# Sheet5.net
KiCad netlist of a schematic drawn in Altium Designer
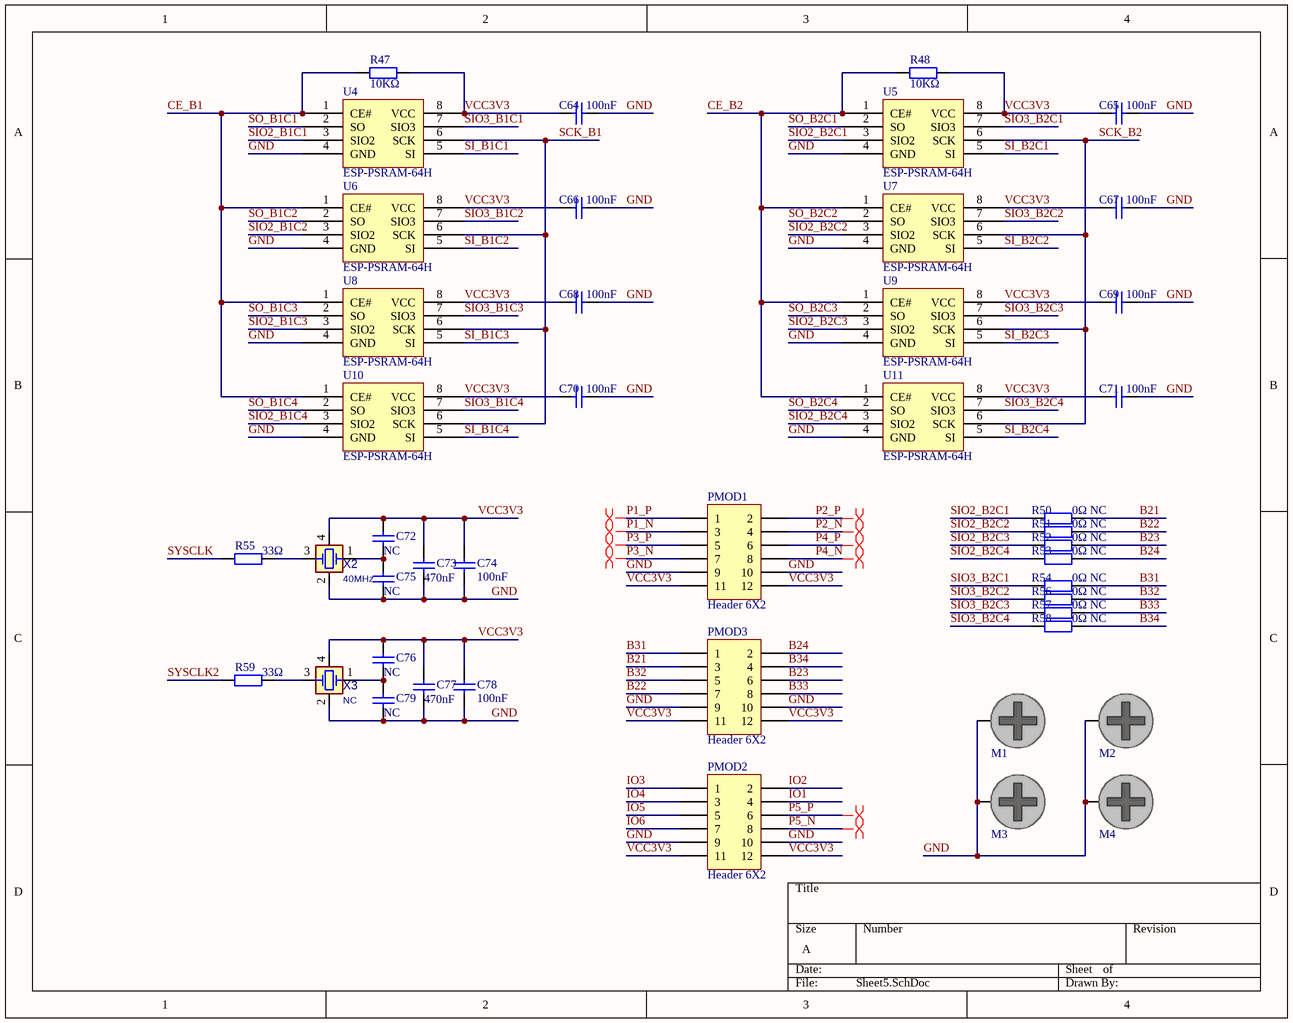
[diagram p0: Sheet5.SchDoc]

(export (version "E")
  (design (tool "Eeschema 10.0.6"))
  (components
    (comp (ref "C64")
      (value "100nF")
      (footprint "1206_C")
      (description "贴片电容")
      (libsource (lib "Cap") (part "1206 100nF (104) 10% 50V"))
    )
    (comp (ref "C65")
      (value "100nF")
      (footprint "1206_C")
      (description "贴片电容")
      (libsource (lib "Cap") (part "1206 100nF (104) 10% 50V"))
    )
    (comp (ref "C66")
      (value "100nF")
      (footprint "1206_C")
      (description "贴片电容")
      (libsource (lib "Cap") (part "1206 100nF (104) 10% 50V"))
    )
    (comp (ref "C67")
      (value "100nF")
      (footprint "1206_C")
      (description "贴片电容")
      (libsource (lib "Cap") (part "1206 100nF (104) 10% 50V"))
    )
    (comp (ref "C68")
      (value "100nF")
      (footprint "1206_C")
      (description "贴片电容")
      (libsource (lib "Cap") (part "1206 100nF (104) 10% 50V"))
    )
    (comp (ref "C69")
      (value "100nF")
      (footprint "1206_C")
      (description "贴片电容")
      (libsource (lib "Cap") (part "1206 100nF (104) 10% 50V"))
    )
    (comp (ref "C70")
      (value "100nF")
      (footprint "1206_C")
      (description "贴片电容")
      (libsource (lib "Cap") (part "1206 100nF (104) 10% 50V"))
    )
    (comp (ref "C71")
      (value "100nF")
      (footprint "1206_C")
      (description "贴片电容")
      (libsource (lib "Cap") (part "1206 100nF (104) 10% 50V"))
    )
    (comp (ref "C72")
      (value "NC")
      (footprint "0402_C")
      (description "贴片电容")
      (libsource (lib "Cap") (part "0402 470nF (474) 10% 10V"))
    )
    (comp (ref "C73")
      (value "470nF")
      (footprint "0402_C")
      (description "贴片电容")
      (libsource (lib "Cap") (part "0402 470nF (474) 10% 10V"))
    )
    (comp (ref "C74")
      (value "100nF")
      (footprint "1206_C")
      (description "贴片电容")
      (libsource (lib "Cap") (part "1206 100nF (104) 10% 50V"))
    )
    (comp (ref "C75")
      (value "NC")
      (footprint "0402_C")
      (description "贴片电容")
      (libsource (lib "Cap") (part "0402 470nF (474) 10% 10V"))
    )
    (comp (ref "C76")
      (value "NC")
      (footprint "0402_C")
      (description "贴片电容")
      (libsource (lib "Cap") (part "0402 470nF (474) 10% 10V"))
    )
    (comp (ref "C77")
      (value "470nF")
      (footprint "0402_C")
      (description "贴片电容")
      (libsource (lib "Cap") (part "0402 470nF (474) 10% 10V"))
    )
    (comp (ref "C78")
      (value "100nF")
      (footprint "1206_C")
      (description "贴片电容")
      (libsource (lib "Cap") (part "1206 100nF (104) 10% 50V"))
    )
    (comp (ref "C79")
      (value "NC")
      (footprint "0402_C")
      (description "贴片电容")
      (libsource (lib "Cap") (part "0402 470nF (474) 10% 10V"))
    )
    (comp (ref "M1")
      (value "DNP/MH")
      (footprint "SCMH_M2")
      (description "SCREW mouting, M2, 2.0mm diameter and 4.0mm PanHead")
      (libsource (lib "Mechanical") (part "SCMH_M2"))
    )
    (comp (ref "M2")
      (value "DNP/MH")
      (footprint "SCMH_M2")
      (description "SCREW mouting, M2, 2.0mm diameter and 4.0mm PanHead")
      (libsource (lib "Mechanical") (part "SCMH_M2"))
    )
    (comp (ref "M3")
      (value "DNP/MH")
      (footprint "SCMH_M2")
      (description "SCREW mouting, M2, 2.0mm diameter and 4.0mm PanHead")
      (libsource (lib "Mechanical") (part "SCMH_M2"))
    )
    (comp (ref "M4")
      (value "DNP/MH")
      (footprint "SCMH_M2")
      (description "SCREW mouting, M2, 2.0mm diameter and 4.0mm PanHead")
      (libsource (lib "Mechanical") (part "SCMH_M2"))
    )
    (comp (ref "PMOD1")
      (value "Header 6X2")
      (footprint "HDR2X6")
      (description "Header, 6-Pin, Dual row")
      (fields (field (name "PUBLISHER") "Altium Limited"))
      (libsource (lib "Miscellaneous Connectors") (part "Header 6X2"))
    )
    (comp (ref "PMOD2")
      (value "Header 6X2")
      (footprint "HDR2X6")
      (description "Header, 6-Pin, Dual row")
      (fields (field (name "PUBLISHER") "Altium Limited"))
      (libsource (lib "Miscellaneous Connectors") (part "Header 6X2"))
    )
    (comp (ref "PMOD3")
      (value "Header 6X2")
      (footprint "HDR2X6")
      (description "Header, 6-Pin, Dual row")
      (fields (field (name "PUBLISHER") "Altium Limited"))
      (libsource (lib "Miscellaneous Connectors") (part "Header 6X2"))
    )
    (comp (ref "R47")
      (value "10KΩ")
      (footprint "1206_R")
      (description "贴片电阻")
      (libsource (lib "RES") (part "1206 10KΩ (1002) 1%"))
    )
    (comp (ref "R48")
      (value "10KΩ")
      (footprint "1206_R")
      (description "贴片电阻")
      (libsource (lib "RES") (part "1206 10KΩ (1002) 1%"))
    )
    (comp (ref "R50")
      (value "0Ω NC")
      (footprint "0603_R")
      (description "贴片电阻")
      (libsource (lib "RES") (part "0603 0Ω (0R0) 1%"))
    )
    (comp (ref "R51")
      (value "0Ω NC")
      (footprint "0603_R")
      (description "贴片电阻")
      (libsource (lib "RES") (part "0603 0Ω (0R0) 1%"))
    )
    (comp (ref "R52")
      (value "0Ω NC")
      (footprint "0603_R")
      (description "贴片电阻")
      (libsource (lib "RES") (part "0603 0Ω (0R0) 1%"))
    )
    (comp (ref "R53")
      (value "0Ω NC")
      (footprint "0603_R")
      (description "贴片电阻")
      (libsource (lib "RES") (part "0603 0Ω (0R0) 1%"))
    )
    (comp (ref "R54")
      (value "0Ω NC")
      (footprint "0603_R")
      (description "贴片电阻")
      (libsource (lib "RES") (part "0603 0Ω (0R0) 1%"))
    )
    (comp (ref "R55")
      (value "33Ω")
      (footprint "0603_R")
      (description "贴片电阻")
      (libsource (lib "RES") (part "0603 33Ω (33R0) 1%"))
    )
    (comp (ref "R56")
      (value "0Ω NC")
      (footprint "0603_R")
      (description "贴片电阻")
      (libsource (lib "RES") (part "0603 0Ω (0R0) 1%"))
    )
    (comp (ref "R57")
      (value "0Ω NC")
      (footprint "0603_R")
      (description "贴片电阻")
      (libsource (lib "RES") (part "0603 0Ω (0R0) 1%"))
    )
    (comp (ref "R58")
      (value "0Ω NC")
      (footprint "0603_R")
      (description "贴片电阻")
      (libsource (lib "RES") (part "0603 0Ω (0R0) 1%"))
    )
    (comp (ref "R59")
      (value "33Ω")
      (footprint "0603_R")
      (description "贴片电阻")
      (libsource (lib "RES") (part "0603 33Ω (33R0) 1%"))
    )
    (comp (ref "U4")
      (value "ESP-PSRAM-64H")
      (footprint "SOIC-8_150mil")
      (description "PSRAM, 150mil SOP-8")
      (libsource (lib "IC") (part "EEPROM/AT24C256C-SSHL-T_[C6482]"))
    )
    (comp (ref "U5")
      (value "ESP-PSRAM-64H")
      (footprint "SOIC-8_150mil")
      (description "PSRAM, 150mil SOP-8")
      (libsource (lib "IC") (part "EEPROM/AT24C256C-SSHL-T_[C6482]"))
    )
    (comp (ref "U6")
      (value "ESP-PSRAM-64H")
      (footprint "SOIC-8_150mil")
      (description "PSRAM, 150mil SOP-8")
      (libsource (lib "IC") (part "EEPROM/AT24C256C-SSHL-T_[C6482]"))
    )
    (comp (ref "U7")
      (value "ESP-PSRAM-64H")
      (footprint "SOIC-8_150mil")
      (description "PSRAM, 150mil SOP-8")
      (libsource (lib "IC") (part "EEPROM/AT24C256C-SSHL-T_[C6482]"))
    )
    (comp (ref "U8")
      (value "ESP-PSRAM-64H")
      (footprint "SOIC-8_150mil")
      (description "PSRAM, 150mil SOP-8")
      (libsource (lib "IC") (part "EEPROM/AT24C256C-SSHL-T_[C6482]"))
    )
    (comp (ref "U9")
      (value "ESP-PSRAM-64H")
      (footprint "SOIC-8_150mil")
      (description "PSRAM, 150mil SOP-8")
      (libsource (lib "IC") (part "EEPROM/AT24C256C-SSHL-T_[C6482]"))
    )
    (comp (ref "U10")
      (value "ESP-PSRAM-64H")
      (footprint "SOIC-8_150mil")
      (description "PSRAM, 150mil SOP-8")
      (libsource (lib "IC") (part "EEPROM/AT24C256C-SSHL-T_[C6482]"))
    )
    (comp (ref "U11")
      (value "ESP-PSRAM-64H")
      (footprint "SOIC-8_150mil")
      (description "PSRAM, 150mil SOP-8")
      (libsource (lib "IC") (part "EEPROM/AT24C256C-SSHL-T_[C6482]"))
    )
    (comp (ref "X2")
      (value "40MHz")
      (footprint "XTL_4_3225")
      (description "CRYSTAL 40.00 MHZ 4pF, 10PPM")
      (fields (field (name "MANF") "ABRACON") (field (name "MANF_P#") "ABM8W-40.0000MHZ-4-B1U-T3"))
      (libsource (lib "Crystal Oscillator") (part "XTL_4_40MHz_3225A"))
    )
    (comp (ref "X3")
      (value "NC")
      (footprint "XTL_4_3225")
      (description "CRYSTAL 40.00 MHZ 4pF, 10PPM")
      (fields (field (name "MANF") "ABRACON") (field (name "MANF_P#") "ABM8W-40.0000MHZ-4-B1U-T3"))
      (libsource (lib "Crystal Oscillator") (part "XTL_4_40MHz_3225A"))
    )
  )
  (nets
    (net (code "1") (name "/B21") (class "Default")
      (node (ref "PMOD3") (pin "3") (pinfunction "3_3") (pintype "passive"))
      (node (ref "R50") (pin "2") (pinfunction "2_2") (pintype "passive"))
    )
    (net (code "2") (name "/B22") (class "Default")
      (node (ref "PMOD3") (pin "7") (pinfunction "7_7") (pintype "passive"))
      (node (ref "R51") (pin "2") (pinfunction "2_2") (pintype "passive"))
    )
    (net (code "3") (name "/B23") (class "Default")
      (node (ref "PMOD3") (pin "6") (pinfunction "6_6") (pintype "passive"))
      (node (ref "R52") (pin "2") (pinfunction "2_2") (pintype "passive"))
    )
    (net (code "4") (name "/B24") (class "Default")
      (node (ref "PMOD3") (pin "2") (pinfunction "2_2") (pintype "passive"))
      (node (ref "R53") (pin "2") (pinfunction "2_2") (pintype "passive"))
    )
    (net (code "5") (name "/B31") (class "Default")
      (node (ref "PMOD3") (pin "1") (pinfunction "1_1") (pintype "passive"))
      (node (ref "R54") (pin "2") (pinfunction "2_2") (pintype "passive"))
    )
    (net (code "6") (name "/B32") (class "Default")
      (node (ref "PMOD3") (pin "5") (pinfunction "5_5") (pintype "passive"))
      (node (ref "R56") (pin "2") (pinfunction "2_2") (pintype "passive"))
    )
    (net (code "7") (name "/B33") (class "Default")
      (node (ref "PMOD3") (pin "8") (pinfunction "8_8") (pintype "passive"))
      (node (ref "R57") (pin "2") (pinfunction "2_2") (pintype "passive"))
    )
    (net (code "8") (name "/B34") (class "Default")
      (node (ref "PMOD3") (pin "4") (pinfunction "4_4") (pintype "passive"))
      (node (ref "R58") (pin "2") (pinfunction "2_2") (pintype "passive"))
    )
    (net (code "9") (name "/CE_B1") (class "Default")
      (node (ref "R47") (pin "2") (pinfunction "2_2") (pintype "passive"))
      (node (ref "U10") (pin "1") (pinfunction "CE#_1") (pintype "passive"))
      (node (ref "U4") (pin "1") (pinfunction "CE#_1") (pintype "passive"))
      (node (ref "U6") (pin "1") (pinfunction "CE#_1") (pintype "passive"))
      (node (ref "U8") (pin "1") (pinfunction "CE#_1") (pintype "passive"))
    )
    (net (code "10") (name "/CE_B2") (class "Default")
      (node (ref "R48") (pin "2") (pinfunction "2_2") (pintype "passive"))
      (node (ref "U11") (pin "1") (pinfunction "CE#_1") (pintype "passive"))
      (node (ref "U5") (pin "1") (pinfunction "CE#_1") (pintype "passive"))
      (node (ref "U7") (pin "1") (pinfunction "CE#_1") (pintype "passive"))
      (node (ref "U9") (pin "1") (pinfunction "CE#_1") (pintype "passive"))
    )
    (net (code "11") (name "/GND") (class "Default")
      (node (ref "C64") (pin "1") (pinfunction "1_1") (pintype "passive"))
      (node (ref "C65") (pin "1") (pinfunction "1_1") (pintype "passive"))
      (node (ref "C66") (pin "1") (pinfunction "1_1") (pintype "passive"))
      (node (ref "C67") (pin "1") (pinfunction "1_1") (pintype "passive"))
      (node (ref "C68") (pin "1") (pinfunction "1_1") (pintype "passive"))
      (node (ref "C69") (pin "1") (pinfunction "1_1") (pintype "passive"))
      (node (ref "C70") (pin "1") (pinfunction "1_1") (pintype "passive"))
      (node (ref "C71") (pin "1") (pinfunction "1_1") (pintype "passive"))
      (node (ref "C73") (pin "2") (pinfunction "2_2") (pintype "passive"))
      (node (ref "C74") (pin "1") (pinfunction "1_1") (pintype "passive"))
      (node (ref "C75") (pin "2") (pinfunction "2_2") (pintype "passive"))
      (node (ref "C77") (pin "2") (pinfunction "2_2") (pintype "passive"))
      (node (ref "C78") (pin "1") (pinfunction "1_1") (pintype "passive"))
      (node (ref "C79") (pin "2") (pinfunction "2_2") (pintype "passive"))
      (node (ref "M1") (pin "1") (pinfunction "1_1") (pintype "passive"))
      (node (ref "M2") (pin "1") (pinfunction "1_1") (pintype "passive"))
      (node (ref "M3") (pin "1") (pinfunction "1_1") (pintype "passive"))
      (node (ref "M4") (pin "1") (pinfunction "1_1") (pintype "passive"))
      (node (ref "PMOD1") (pin "10") (pinfunction "10_10") (pintype "passive"))
      (node (ref "PMOD1") (pin "9") (pinfunction "9_9") (pintype "passive"))
      (node (ref "PMOD2") (pin "10") (pinfunction "10_10") (pintype "passive"))
      (node (ref "PMOD2") (pin "9") (pinfunction "9_9") (pintype "passive"))
      (node (ref "PMOD3") (pin "10") (pinfunction "10_10") (pintype "passive"))
      (node (ref "PMOD3") (pin "9") (pinfunction "9_9") (pintype "passive"))
      (node (ref "U10") (pin "4") (pinfunction "GND_4") (pintype "passive"))
      (node (ref "U11") (pin "4") (pinfunction "GND_4") (pintype "passive"))
      (node (ref "U4") (pin "4") (pinfunction "GND_4") (pintype "passive"))
      (node (ref "U5") (pin "4") (pinfunction "GND_4") (pintype "passive"))
      (node (ref "U6") (pin "4") (pinfunction "GND_4") (pintype "passive"))
      (node (ref "U7") (pin "4") (pinfunction "GND_4") (pintype "passive"))
      (node (ref "U8") (pin "4") (pinfunction "GND_4") (pintype "passive"))
      (node (ref "U9") (pin "4") (pinfunction "GND_4") (pintype "passive"))
      (node (ref "X2") (pin "2") (pinfunction "GND1_2") (pintype "passive"))
      (node (ref "X3") (pin "2") (pinfunction "GND1_2") (pintype "passive"))
    )
    (net (code "12") (name "/IO1") (class "Default")
      (node (ref "PMOD2") (pin "4") (pinfunction "4_4") (pintype "passive"))
    )
    (net (code "13") (name "/IO2") (class "Default")
      (node (ref "PMOD2") (pin "2") (pinfunction "2_2") (pintype "passive"))
    )
    (net (code "14") (name "/IO3") (class "Default")
      (node (ref "PMOD2") (pin "1") (pinfunction "1_1") (pintype "passive"))
    )
    (net (code "15") (name "/IO4") (class "Default")
      (node (ref "PMOD2") (pin "3") (pinfunction "3_3") (pintype "passive"))
    )
    (net (code "16") (name "/IO5") (class "Default")
      (node (ref "PMOD2") (pin "5") (pinfunction "5_5") (pintype "passive"))
    )
    (net (code "17") (name "/IO6") (class "Default")
      (node (ref "PMOD2") (pin "7") (pinfunction "7_7") (pintype "passive"))
    )
    (net (code "18") (name "/P1_N") (class "Default")
      (node (ref "PMOD1") (pin "3") (pinfunction "3_3") (pintype "passive"))
    )
    (net (code "19") (name "/P1_P") (class "Default")
      (node (ref "PMOD1") (pin "1") (pinfunction "1_1") (pintype "passive"))
    )
    (net (code "20") (name "/P2_N") (class "Default")
      (node (ref "PMOD1") (pin "4") (pinfunction "4_4") (pintype "passive"))
    )
    (net (code "21") (name "/P2_P") (class "Default")
      (node (ref "PMOD1") (pin "2") (pinfunction "2_2") (pintype "passive"))
    )
    (net (code "22") (name "/P3_N") (class "Default")
      (node (ref "PMOD1") (pin "7") (pinfunction "7_7") (pintype "passive"))
    )
    (net (code "23") (name "/P3_P") (class "Default")
      (node (ref "PMOD1") (pin "5") (pinfunction "5_5") (pintype "passive"))
    )
    (net (code "24") (name "/P4_N") (class "Default")
      (node (ref "PMOD1") (pin "8") (pinfunction "8_8") (pintype "passive"))
    )
    (net (code "25") (name "/P4_P") (class "Default")
      (node (ref "PMOD1") (pin "6") (pinfunction "6_6") (pintype "passive"))
    )
    (net (code "26") (name "/P5_N") (class "Default")
      (node (ref "PMOD2") (pin "8") (pinfunction "8_8") (pintype "passive"))
    )
    (net (code "27") (name "/P5_P") (class "Default")
      (node (ref "PMOD2") (pin "6") (pinfunction "6_6") (pintype "passive"))
    )
    (net (code "28") (name "/SCK_B1") (class "Default")
      (node (ref "U10") (pin "6") (pinfunction "SCK_6") (pintype "passive"))
      (node (ref "U4") (pin "6") (pinfunction "SCK_6") (pintype "passive"))
      (node (ref "U6") (pin "6") (pinfunction "SCK_6") (pintype "passive"))
      (node (ref "U8") (pin "6") (pinfunction "SCK_6") (pintype "passive"))
    )
    (net (code "29") (name "/SCK_B2") (class "Default")
      (node (ref "U11") (pin "6") (pinfunction "SCK_6") (pintype "passive"))
      (node (ref "U5") (pin "6") (pinfunction "SCK_6") (pintype "passive"))
      (node (ref "U7") (pin "6") (pinfunction "SCK_6") (pintype "passive"))
      (node (ref "U9") (pin "6") (pinfunction "SCK_6") (pintype "passive"))
    )
    (net (code "30") (name "/SIO2_B1C1") (class "Default")
      (node (ref "U4") (pin "3") (pinfunction "SIO2_3") (pintype "passive"))
    )
    (net (code "31") (name "/SIO2_B1C2") (class "Default")
      (node (ref "U6") (pin "3") (pinfunction "SIO2_3") (pintype "passive"))
    )
    (net (code "32") (name "/SIO2_B1C3") (class "Default")
      (node (ref "U8") (pin "3") (pinfunction "SIO2_3") (pintype "passive"))
    )
    (net (code "33") (name "/SIO2_B1C4") (class "Default")
      (node (ref "U10") (pin "3") (pinfunction "SIO2_3") (pintype "passive"))
    )
    (net (code "34") (name "/SIO2_B2C1") (class "Default")
      (node (ref "R50") (pin "1") (pinfunction "1_1") (pintype "passive"))
      (node (ref "U5") (pin "3") (pinfunction "SIO2_3") (pintype "passive"))
    )
    (net (code "35") (name "/SIO2_B2C2") (class "Default")
      (node (ref "R51") (pin "1") (pinfunction "1_1") (pintype "passive"))
      (node (ref "U7") (pin "3") (pinfunction "SIO2_3") (pintype "passive"))
    )
    (net (code "36") (name "/SIO2_B2C3") (class "Default")
      (node (ref "R52") (pin "1") (pinfunction "1_1") (pintype "passive"))
      (node (ref "U9") (pin "3") (pinfunction "SIO2_3") (pintype "passive"))
    )
    (net (code "37") (name "/SIO2_B2C4") (class "Default")
      (node (ref "R53") (pin "1") (pinfunction "1_1") (pintype "passive"))
      (node (ref "U11") (pin "3") (pinfunction "SIO2_3") (pintype "passive"))
    )
    (net (code "38") (name "/SIO3_B1C1") (class "Default")
      (node (ref "U4") (pin "7") (pinfunction "SIO3_7") (pintype "passive"))
    )
    (net (code "39") (name "/SIO3_B1C2") (class "Default")
      (node (ref "U6") (pin "7") (pinfunction "SIO3_7") (pintype "passive"))
    )
    (net (code "40") (name "/SIO3_B1C3") (class "Default")
      (node (ref "U8") (pin "7") (pinfunction "SIO3_7") (pintype "passive"))
    )
    (net (code "41") (name "/SIO3_B1C4") (class "Default")
      (node (ref "U10") (pin "7") (pinfunction "SIO3_7") (pintype "passive"))
    )
    (net (code "42") (name "/SIO3_B2C1") (class "Default")
      (node (ref "R54") (pin "1") (pinfunction "1_1") (pintype "passive"))
      (node (ref "U5") (pin "7") (pinfunction "SIO3_7") (pintype "passive"))
    )
    (net (code "43") (name "/SIO3_B2C2") (class "Default")
      (node (ref "R56") (pin "1") (pinfunction "1_1") (pintype "passive"))
      (node (ref "U7") (pin "7") (pinfunction "SIO3_7") (pintype "passive"))
    )
    (net (code "44") (name "/SIO3_B2C3") (class "Default")
      (node (ref "R57") (pin "1") (pinfunction "1_1") (pintype "passive"))
      (node (ref "U9") (pin "7") (pinfunction "SIO3_7") (pintype "passive"))
    )
    (net (code "45") (name "/SIO3_B2C4") (class "Default")
      (node (ref "R58") (pin "1") (pinfunction "1_1") (pintype "passive"))
      (node (ref "U11") (pin "7") (pinfunction "SIO3_7") (pintype "passive"))
    )
    (net (code "46") (name "/SI_B1C1") (class "Default")
      (node (ref "U4") (pin "5") (pinfunction "SI_5") (pintype "passive"))
    )
    (net (code "47") (name "/SI_B1C2") (class "Default")
      (node (ref "U6") (pin "5") (pinfunction "SI_5") (pintype "passive"))
    )
    (net (code "48") (name "/SI_B1C3") (class "Default")
      (node (ref "U8") (pin "5") (pinfunction "SI_5") (pintype "passive"))
    )
    (net (code "49") (name "/SI_B1C4") (class "Default")
      (node (ref "U10") (pin "5") (pinfunction "SI_5") (pintype "passive"))
    )
    (net (code "50") (name "/SI_B2C1") (class "Default")
      (node (ref "U5") (pin "5") (pinfunction "SI_5") (pintype "passive"))
    )
    (net (code "51") (name "/SI_B2C2") (class "Default")
      (node (ref "U7") (pin "5") (pinfunction "SI_5") (pintype "passive"))
    )
    (net (code "52") (name "/SI_B2C3") (class "Default")
      (node (ref "U9") (pin "5") (pinfunction "SI_5") (pintype "passive"))
    )
    (net (code "53") (name "/SI_B2C4") (class "Default")
      (node (ref "U11") (pin "5") (pinfunction "SI_5") (pintype "passive"))
    )
    (net (code "54") (name "/SO_B1C1") (class "Default")
      (node (ref "U4") (pin "2") (pinfunction "SO_2") (pintype "passive"))
    )
    (net (code "55") (name "/SO_B1C2") (class "Default")
      (node (ref "U6") (pin "2") (pinfunction "SO_2") (pintype "passive"))
    )
    (net (code "56") (name "/SO_B1C3") (class "Default")
      (node (ref "U8") (pin "2") (pinfunction "SO_2") (pintype "passive"))
    )
    (net (code "57") (name "/SO_B1C4") (class "Default")
      (node (ref "U10") (pin "2") (pinfunction "SO_2") (pintype "passive"))
    )
    (net (code "58") (name "/SO_B2C1") (class "Default")
      (node (ref "U5") (pin "2") (pinfunction "SO_2") (pintype "passive"))
    )
    (net (code "59") (name "/SO_B2C2") (class "Default")
      (node (ref "U7") (pin "2") (pinfunction "SO_2") (pintype "passive"))
    )
    (net (code "60") (name "/SO_B2C3") (class "Default")
      (node (ref "U9") (pin "2") (pinfunction "SO_2") (pintype "passive"))
    )
    (net (code "61") (name "/SO_B2C4") (class "Default")
      (node (ref "U11") (pin "2") (pinfunction "SO_2") (pintype "passive"))
    )
    (net (code "62") (name "/SYSCLK") (class "Default")
      (node (ref "R55") (pin "1") (pinfunction "1_1") (pintype "passive"))
    )
    (net (code "63") (name "/SYSCLK2") (class "Default")
      (node (ref "R59") (pin "1") (pinfunction "1_1") (pintype "passive"))
    )
    (net (code "64") (name "/VCC3V3") (class "Default")
      (node (ref "C64") (pin "2") (pinfunction "2_2") (pintype "passive"))
      (node (ref "C65") (pin "2") (pinfunction "2_2") (pintype "passive"))
      (node (ref "C66") (pin "2") (pinfunction "2_2") (pintype "passive"))
      (node (ref "C67") (pin "2") (pinfunction "2_2") (pintype "passive"))
      (node (ref "C68") (pin "2") (pinfunction "2_2") (pintype "passive"))
      (node (ref "C69") (pin "2") (pinfunction "2_2") (pintype "passive"))
      (node (ref "C70") (pin "2") (pinfunction "2_2") (pintype "passive"))
      (node (ref "C71") (pin "2") (pinfunction "2_2") (pintype "passive"))
      (node (ref "C72") (pin "1") (pinfunction "1_1") (pintype "passive"))
      (node (ref "C73") (pin "1") (pinfunction "1_1") (pintype "passive"))
      (node (ref "C74") (pin "2") (pinfunction "2_2") (pintype "passive"))
      (node (ref "C76") (pin "1") (pinfunction "1_1") (pintype "passive"))
      (node (ref "C77") (pin "1") (pinfunction "1_1") (pintype "passive"))
      (node (ref "C78") (pin "2") (pinfunction "2_2") (pintype "passive"))
      (node (ref "PMOD1") (pin "11") (pinfunction "11_11") (pintype "passive"))
      (node (ref "PMOD1") (pin "12") (pinfunction "12_12") (pintype "passive"))
      (node (ref "PMOD2") (pin "11") (pinfunction "11_11") (pintype "passive"))
      (node (ref "PMOD2") (pin "12") (pinfunction "12_12") (pintype "passive"))
      (node (ref "PMOD3") (pin "11") (pinfunction "11_11") (pintype "passive"))
      (node (ref "PMOD3") (pin "12") (pinfunction "12_12") (pintype "passive"))
      (node (ref "R47") (pin "1") (pinfunction "1_1") (pintype "passive"))
      (node (ref "R48") (pin "1") (pinfunction "1_1") (pintype "passive"))
      (node (ref "U10") (pin "8") (pinfunction "VCC_8") (pintype "passive"))
      (node (ref "U11") (pin "8") (pinfunction "VCC_8") (pintype "passive"))
      (node (ref "U4") (pin "8") (pinfunction "VCC_8") (pintype "passive"))
      (node (ref "U5") (pin "8") (pinfunction "VCC_8") (pintype "passive"))
      (node (ref "U6") (pin "8") (pinfunction "VCC_8") (pintype "passive"))
      (node (ref "U7") (pin "8") (pinfunction "VCC_8") (pintype "passive"))
      (node (ref "U8") (pin "8") (pinfunction "VCC_8") (pintype "passive"))
      (node (ref "U9") (pin "8") (pinfunction "VCC_8") (pintype "passive"))
      (node (ref "X2") (pin "4") (pinfunction "GND2_4") (pintype "passive"))
      (node (ref "X3") (pin "4") (pinfunction "GND2_4") (pintype "passive"))
    )
    (net (code "65") (name "Net-(X2-XA)") (class "Default")
      (node (ref "C72") (pin "2") (pinfunction "2_2") (pintype "passive"))
      (node (ref "C75") (pin "1") (pinfunction "1_1") (pintype "passive"))
      (node (ref "X2") (pin "1") (pinfunction "XA_1") (pintype "passive"))
    )
    (net (code "66") (name "Net-(X2-XB)") (class "Default")
      (node (ref "R55") (pin "2") (pinfunction "2_2") (pintype "passive"))
      (node (ref "X2") (pin "3") (pinfunction "XB_3") (pintype "passive"))
    )
    (net (code "67") (name "Net-(X3-XA)") (class "Default")
      (node (ref "C76") (pin "2") (pinfunction "2_2") (pintype "passive"))
      (node (ref "C79") (pin "1") (pinfunction "1_1") (pintype "passive"))
      (node (ref "X3") (pin "1") (pinfunction "XA_1") (pintype "passive"))
    )
    (net (code "68") (name "Net-(X3-XB)") (class "Default")
      (node (ref "R59") (pin "2") (pinfunction "2_2") (pintype "passive"))
      (node (ref "X3") (pin "3") (pinfunction "XB_3") (pintype "passive"))
    )
  )
)
